# Power_Supply.net
KiCad netlist of a schematic drawn in Altium Designer
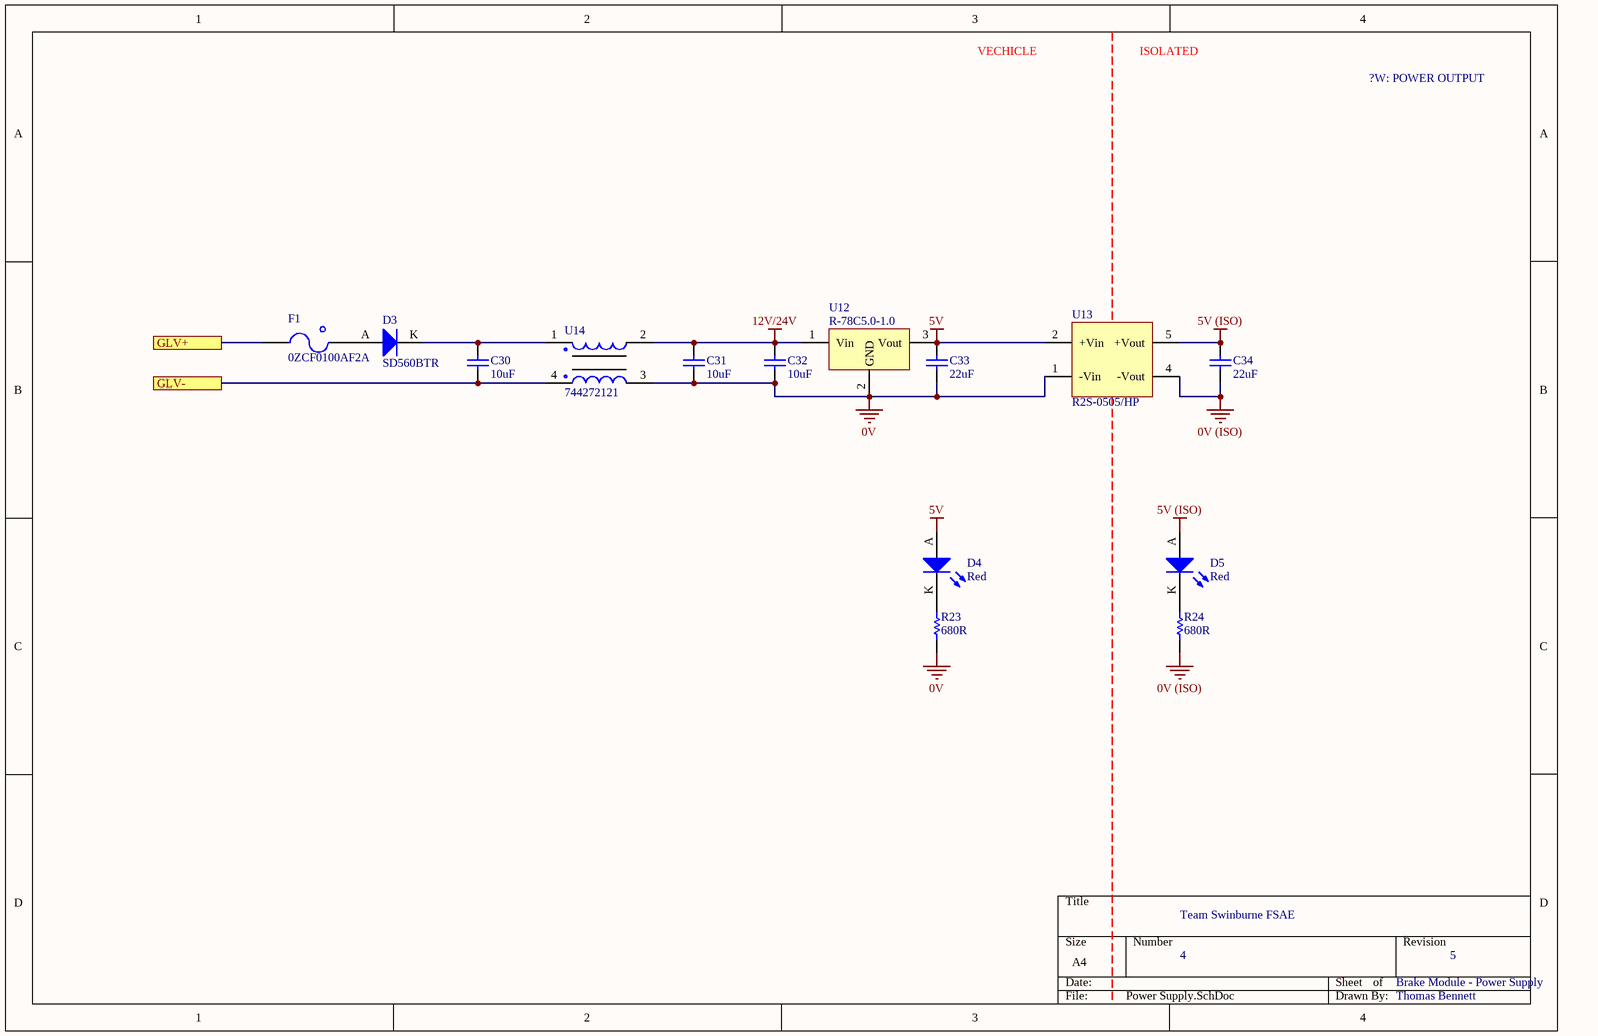
[diagram p0: Power Supply.SchDoc]

(export (version "E")
  (design (tool "Eeschema 10.0.6"))
  (components
    (comp (ref "C30")
      (value "10uF")
      (footprint "0805")
      (fields
        (field (name "PART NUMBER") "GRM21BR6YA106KE43L")
        (field (name "TOLERANCE") "10%")
        (field (name "MANUFACTURER") "muRata")
      )
      (libsource (lib "ts_20-standard-library") (part "Capacitor"))
    )
    (comp (ref "C31")
      (value "10uF")
      (footprint "0805")
      (fields
        (field (name "PART NUMBER") "GRM21BR6YA106KE43L")
        (field (name "TOLERANCE") "10%")
        (field (name "MANUFACTURER") "muRata")
      )
      (libsource (lib "ts_20-standard-library") (part "Capacitor"))
    )
    (comp (ref "C32")
      (value "10uF")
      (footprint "0805")
      (fields
        (field (name "PART NUMBER") "GRM21BR6YA106KE43L")
        (field (name "TOLERANCE") "10%")
        (field (name "MANUFACTURER") "muRata")
      )
      (libsource (lib "ts_20-standard-library") (part "Capacitor"))
    )
    (comp (ref "C33")
      (value "22uF")
      (footprint "1206")
      (fields
        (field (name "PART NUMBER") "CC1206MKX5R7BB226")
        (field (name "TOLERANCE") "20%")
        (field (name "MANUFACTURER") "YAGEO")
      )
      (libsource (lib "ts_20-standard-library") (part "Capacitor"))
    )
    (comp (ref "C34")
      (value "22uF")
      (footprint "1206")
      (fields
        (field (name "PART NUMBER") "CC1206MKX5R7BB226")
        (field (name "TOLERANCE") "20%")
        (field (name "MANUFACTURER") "YAGEO")
      )
      (libsource (lib "ts_20-standard-library") (part "Capacitor"))
    )
    (comp (ref "D3")
      (value "SD560BTR")
      (footprint "SMB Diode")
      (description "1.2V_F 600V 5A SMB")
      (fields
        (field (name "MANUFACTURER") "SMC Diode Solutions")
        (field (name "DIGIKEY PART NUMBER") "1655-1530-2-ND")
      )
      (libsource (lib "ts_20-standard-library") (part "Diode"))
    )
    (comp (ref "D4")
      (value "Red")
      (footprint "0805 LED")
      (description "Red LED Indication - Discrete 1.75V 0805 (2012 Metric)")
      (fields (field (name "PART NUMBER") "SML-210LTT86") (field (name "MANUFACTURER") "ROHM Semiconductor"))
      (libsource (lib "ts_20-standard-library") (part "LED"))
    )
    (comp (ref "D5")
      (value "Red")
      (footprint "0805 LED")
      (description "Red LED Indication - Discrete 1.75V 0805 (2012 Metric)")
      (fields (field (name "PART NUMBER") "SML-210LTT86") (field (name "MANUFACTURER") "ROHM Semiconductor"))
      (libsource (lib "ts_20-standard-library") (part "LED"))
    )
    (comp (ref "F1")
      (value "0ZCF0100AF2A")
      (footprint "2920")
      (description "PTC RESET FUSE 60V 1A 292")
      (fields
        (field (name "MANUFACTURER") "Littelfuse Inc.")
        (field (name "DIGIKEY PART NUMBER") "507-2070-1-ND")
      )
      (libsource (lib "ts_20-standard-library") (part "PTC Fuse"))
    )
    (comp (ref "R23")
      (value "680R")
      (footprint "0805")
      (fields
        (field (name "PART NUMBER") "RC0805FR07680RL")
        (field (name "MANUFACTURER") "YAGEO")
        (field (name "TOLERANCE") "0.01")
      )
      (libsource (lib "ts_20-standard-library") (part "Resistor"))
    )
    (comp (ref "R24")
      (value "680R")
      (footprint "0805")
      (fields
        (field (name "PART NUMBER") "RC0805FR07680RL")
        (field (name "MANUFACTURER") "YAGEO")
        (field (name "TOLERANCE") "0.01")
      )
      (libsource (lib "ts_20-standard-library") (part "Resistor"))
    )
    (comp (ref "U12")
      (value "R-78C5.0-1.0")
      (footprint "RECOM 3-SIP")
      (description "CONV DC/DC 1A 5V OUT SIP VERT")
      (fields (field (name "MANUFACTURER") "Recom") (field (name "DIGIKEY PART NUMBER") "945-1395-5-ND"))
      (libsource (lib "ts_20-standard-library") (part "R-78C5.0-1.0"))
    )
    (comp (ref "U13")
      (value "R2S-0505/HP")
      (footprint "RECOM 8-SMD (5 Pin)")
      (description "Isolated Module DC DC Converter 1 Output 3.3V 606mA 4.5V - 5.5V Input")
      (fields (field (name "MANUFACTURER") "Recom") (field (name "DIGIKEY PART NUMBER") "945-1764-5-ND"))
      (libsource (lib "ts_20-standard-library") (part "R2S-0505/HP"))
    )
    (comp (ref "U14")
      (value "744272121")
      (footprint "Wurth 4-PC Pad")
      (description "120µH @ 100kHz 2 Line Common Mode Choke Surface Mount 460 Ohms @ 30MHz 2.5A DCR 25mOhm")
      (fields
        (field (name "MANUFACTURER") "Wurth Electronics Inc")
        (field (name "DIGIKEY PART NUMBER") "732-1489-1-ND")
      )
      (libsource (lib "ts_20-standard-library") (part "744272121"))
    )
  )
  (nets
    (net (code "1") (name "/GLV+") (class "Default")
      (node (ref "F1") (pin "1") (pinfunction "1_1") (pintype "passive"))
    )
    (net (code "2") (name "/GLV-") (class "Default")
      (node (ref "C30") (pin "1") (pinfunction "1_1") (pintype "passive"))
      (node (ref "U14") (pin "4") (pinfunction "4_4") (pintype "passive"))
    )
    (net (code "3") (name "0V") (class "Default")
      (node (ref "C31") (pin "1") (pinfunction "1_1") (pintype "passive"))
      (node (ref "C32") (pin "1") (pinfunction "1_1") (pintype "passive"))
      (node (ref "C33") (pin "1") (pinfunction "1_1") (pintype "passive"))
      (node (ref "R23") (pin "1") (pinfunction "1_1") (pintype "passive"))
      (node (ref "U12") (pin "2") (pinfunction "GND_2") (pintype "passive"))
      (node (ref "U13") (pin "1") (pinfunction "-Vin_1") (pintype "power_in"))
      (node (ref "U14") (pin "3") (pinfunction "3_3") (pintype "power_in"))
    )
    (net (code "4") (name "0V (ISO)") (class "Default")
      (node (ref "C34") (pin "1") (pinfunction "1_1") (pintype "passive"))
      (node (ref "R24") (pin "1") (pinfunction "1_1") (pintype "passive"))
      (node (ref "U13") (pin "4") (pinfunction "-Vout_4") (pintype "power_in"))
    )
    (net (code "5") (name "5V") (class "Default")
      (node (ref "C33") (pin "2") (pinfunction "2_2") (pintype "passive"))
      (node (ref "D4") (pin "A") (pinfunction "A_A") (pintype "passive"))
      (node (ref "U12") (pin "3") (pinfunction "Vout_3") (pintype "passive"))
      (node (ref "U13") (pin "2") (pinfunction "+Vin_2") (pintype "power_in"))
    )
    (net (code "6") (name "5V (ISO)") (class "Default")
      (node (ref "C34") (pin "2") (pinfunction "2_2") (pintype "passive"))
      (node (ref "D5") (pin "A") (pinfunction "A_A") (pintype "passive"))
      (node (ref "U13") (pin "5") (pinfunction "+Vout_5") (pintype "power_in"))
    )
    (net (code "7") (name "12V{slash}24V") (class "Default")
      (node (ref "C31") (pin "2") (pinfunction "2_2") (pintype "passive"))
      (node (ref "C32") (pin "2") (pinfunction "2_2") (pintype "passive"))
      (node (ref "U12") (pin "1") (pinfunction "Vin_1") (pintype "passive"))
      (node (ref "U14") (pin "2") (pinfunction "2_2") (pintype "passive"))
    )
    (net (code "8") (name "Net-(C30-Pad2)") (class "Default")
      (node (ref "C30") (pin "2") (pinfunction "2_2") (pintype "passive"))
      (node (ref "D3") (pin "K") (pinfunction "K_K") (pintype "passive"))
      (node (ref "U14") (pin "1") (pinfunction "1_1") (pintype "passive"))
    )
    (net (code "9") (name "Net-(D3-PadA)") (class "Default")
      (node (ref "D3") (pin "A") (pinfunction "A_A") (pintype "passive"))
      (node (ref "F1") (pin "2") (pinfunction "2_2") (pintype "passive"))
    )
    (net (code "10") (name "Net-(D4-PadK)") (class "Default")
      (node (ref "D4") (pin "K") (pinfunction "K_K") (pintype "passive"))
      (node (ref "R23") (pin "2") (pinfunction "2_2") (pintype "passive"))
    )
    (net (code "11") (name "Net-(D5-PadK)") (class "Default")
      (node (ref "D5") (pin "K") (pinfunction "K_K") (pintype "passive"))
      (node (ref "R24") (pin "2") (pinfunction "2_2") (pintype "passive"))
    )
  )
)
